# Line-filter.net
KiCad netlist of a schematic drawn in Altium Designer
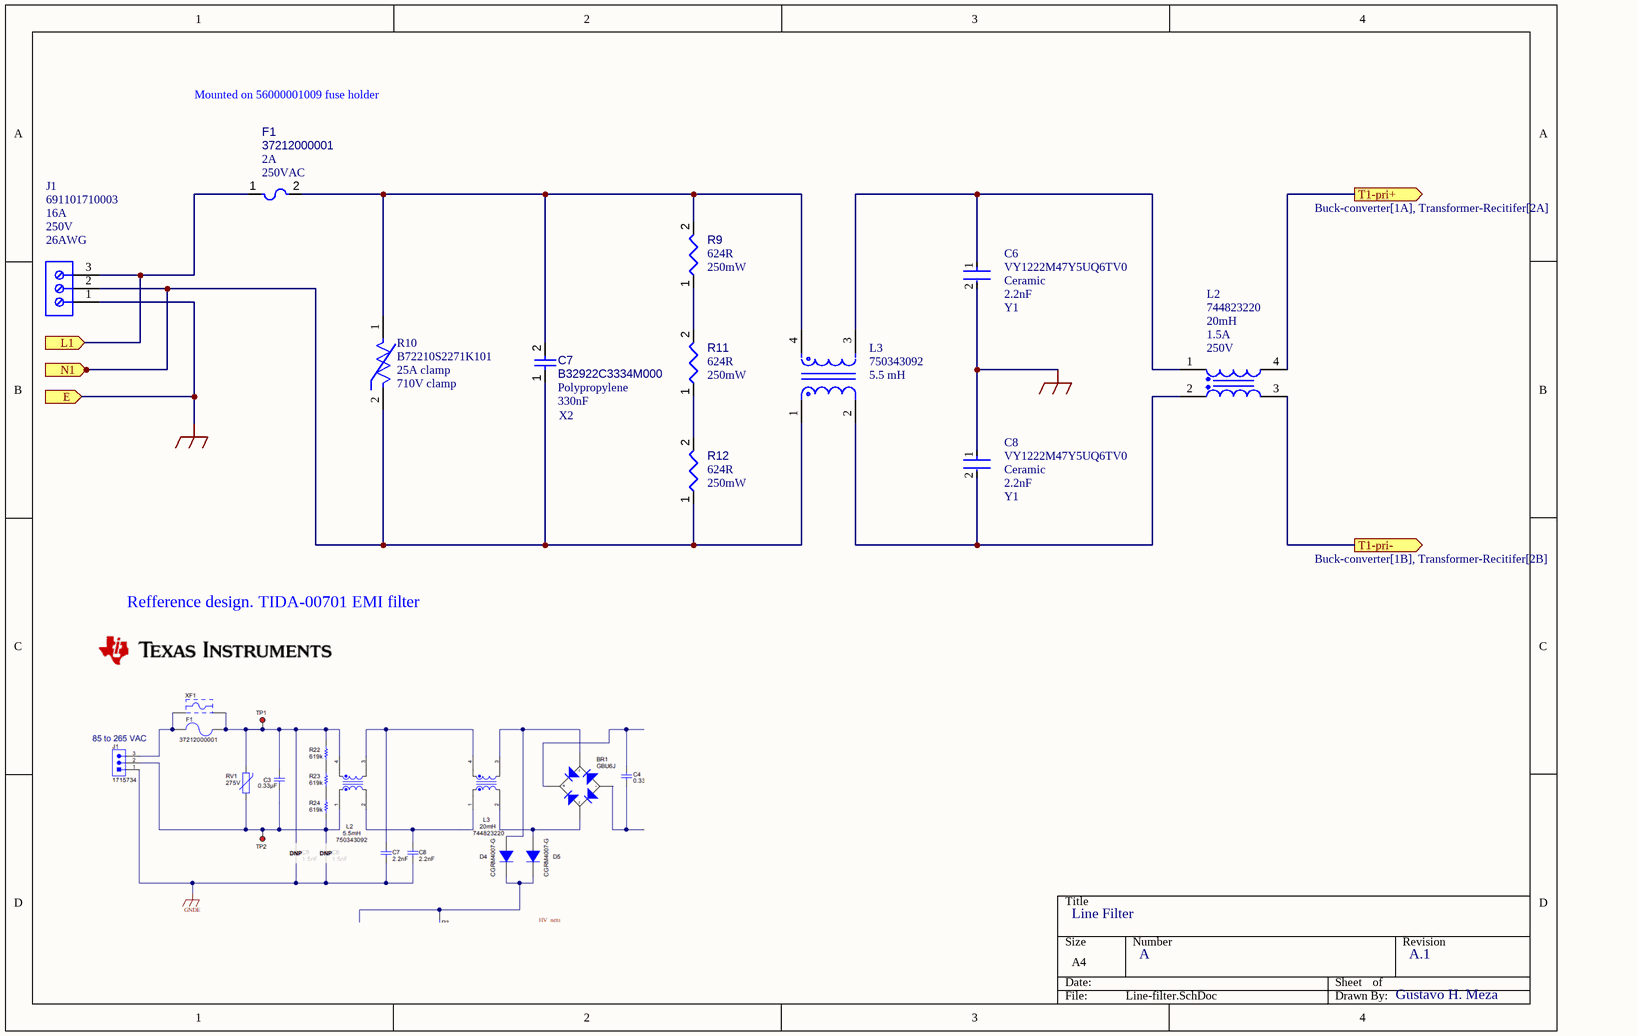
[diagram p0: Line-filter.SchDoc]

(export (version "E")
  (design (tool "Eeschema 10.0.6"))
  (components
    (comp (ref "C6")
      (value "VY1222M47Y5UQ6TV0")
      (footprint "FP-VY1470-MFG")
      (description "CAP CER 2200PF 760VAC Y5U RADIAL")
      (fields
        (field (name "RESISTOR TYPE") "Ceramic")
        (field (name "CAPACITANCE") "2.2nF")
        (field (name "VOLTAGE") "500V")
        (field (name "TOLERANCE") "20%")
        (field (name "SAFETY RATING") "Y1")
      )
      (libsource (lib "Altium Content Vault") (part "11868f565c42a9108669ba33697ecf6"))
    )
    (comp (ref "C7")
      (value "B32922C3334M000")
      (footprint "B32922C3334M000-Footprint-1")
      (description "Film Capacitor, Polypropylene, 630V, 20% +Tol, 20% -Tol, 0.33uF, Through Hole Mount")
      (fields
        (field (name "DIELECTRIC MATERIAL") "Polypropylene")
        (field (name "ALTIUM_VALUE") "330nF")
        (field (name "SAFETY RATING") "X2")
      )
      (libsource (lib "Cetys University") (part "CAP-NP-2"))
    )
    (comp (ref "C8")
      (value "VY1222M47Y5UQ6TV0")
      (footprint "FP-VY1470-MFG")
      (description "CAP CER 2200PF 760VAC Y5U RADIAL")
      (fields
        (field (name "RESISTOR TYPE") "Ceramic")
        (field (name "CAPACITANCE") "2.2nF")
        (field (name "VOLTAGE") "500V")
        (field (name "TOLERANCE") "20%")
        (field (name "SAFETY RATING") "Y1")
      )
      (libsource (lib "Altium Content Vault") (part "11868f565c42a9108669ba33697ecf6"))
    )
    (comp (ref "F1")
      (value "37212000001")
      (footprint "37212000001-Footprint-1")
      (description "Electric Fuse, Time Lag Blow, 2A, 250VAC, 35A (IR), Through Hole, TR5")
      (fields (field (name "CURRENT RATING") "2A") (field (name "VOLTAGE RATING") "250VAC"))
      (libsource (lib "Cetys University") (part "FUSE-2"))
    )
    (comp (ref "J1")
      (value "691101710003")
      (footprint "691101710003")
      (fields
        (field (name "VOLTAGE RATING") "250V")
        (field (name "CURRENT") "16A")
        (field (name "WIRE GAUGE (MIN)") "26AWG")
        (field (name "VOLTAGE") "250V")
      )
      (libsource (lib "Altium Content Vault") (part "TBL - 1R - 03P - Screw"))
    )
    (comp (ref "L2")
      (value "744823220")
      (footprint "WE-CMB_Type M_L23W13.8H25.5")
      (fields
        (field (name "VOLTAGE RATING") "250V")
        (field (name "CURRENT RATING") "1.5A")
        (field (name "INDUCTANCE") "20mH")
      )
      (libsource (lib "Altium Content Vault") (part "WE-CMB"))
    )
    (comp (ref "L3")
      (value "750343092")
      (footprint "FP-750343092-0")
      (description "Power Common Mode Choke")
      (fields (field (name "INDUCTANCE") "5.5 mH"))
      (libsource (lib "Altium Content Vault") (part "7e18bf8fdb9f2485ca2bcdf9073d69f"))
    )
    (comp (ref "R9")
      (value "624R")
      (footprint "RESC3216X06N")
      (fields
        (field (name "TOLERANCE") "1%")
        (field (name "POWER") "250mW")
        (field (name "Comment") "CRCW1206619KFKEA")
      )
      (libsource (lib "Cetys University") (part "RES-2"))
    )
    (comp (ref "R10")
      (value "B72210S2271K101")
      (footprint "FP-B72210S2271K101-MFG")
      (description "VARISTOR 430V 3.5KA DISC 10MM")
      (fields
        (field (name "CLAMPING CURRENT") "25A clamp")
        (field (name "OCTOPART") "https://octopart.com/b72210s2271k101-epcos-42227876")
        (field (name "MANUFACTURER") "EPCOS")
        (field (name "CLAMPING VOLTAGE") "710V clamp")
      )
      (libsource (lib "Altium Content Vault") (part "78a88060d5b7b043d6e48adc4284376"))
    )
    (comp (ref "R11")
      (value "624R")
      (footprint "RESC3216X06N")
      (fields
        (field (name "TOLERANCE") "1%")
        (field (name "POWER") "250mW")
        (field (name "Comment") "CRCW1206619KFKEA")
      )
      (libsource (lib "Cetys University") (part "RES-2"))
    )
    (comp (ref "R12")
      (value "624R")
      (footprint "RESC3216X06N")
      (fields
        (field (name "TOLERANCE") "1%")
        (field (name "POWER") "250mW")
        (field (name "Comment") "CRCW1206619KFKEA")
      )
      (libsource (lib "Cetys University") (part "RES-2"))
    )
  )
  (nets
    (net (code "1") (name "/L1") (class "Default")
      (node (ref "F1") (pin "1") (pinfunction "1_1") (pintype "passive"))
      (node (ref "J1") (pin "3") (pinfunction "3_3") (pintype "passive"))
    )
    (net (code "2") (name "/N1") (class "Default")
      (node (ref "C7") (pin "1") (pinfunction "1_1") (pintype "passive"))
      (node (ref "J1") (pin "2") (pinfunction "2_2") (pintype "passive"))
      (node (ref "L3") (pin "1") (pinfunction "1_1") (pintype "passive"))
      (node (ref "R10") (pin "2") (pinfunction "2_2") (pintype "passive"))
      (node (ref "R12") (pin "1") (pinfunction "1_1") (pintype "passive"))
    )
    (net (code "3") (name "/T1-pri+") (class "Default")
      (node (ref "L2") (pin "4") (pinfunction "4_4") (pintype "passive"))
    )
    (net (code "4") (name "/T1-pri-") (class "Default")
      (node (ref "L2") (pin "3") (pinfunction "3_3") (pintype "passive"))
    )
    (net (code "5") (name "GND") (class "Default")
      (node (ref "C6") (pin "2") (pinfunction "2_2") (pintype "passive"))
      (node (ref "C8") (pin "1") (pinfunction "1_1") (pintype "passive"))
      (node (ref "J1") (pin "1") (pinfunction "1_1") (pintype "passive"))
    )
    (net (code "6") (name "Net-(C6-Pad1)") (class "Default")
      (node (ref "C6") (pin "1") (pinfunction "1_1") (pintype "passive"))
      (node (ref "L2") (pin "1") (pinfunction "1_1") (pintype "passive"))
      (node (ref "L3") (pin "3") (pinfunction "3_3") (pintype "passive"))
    )
    (net (code "7") (name "Net-(C7-Pad2)") (class "Default")
      (node (ref "C7") (pin "2") (pinfunction "2_2") (pintype "passive"))
      (node (ref "F1") (pin "2") (pinfunction "2_2") (pintype "passive"))
      (node (ref "L3") (pin "4") (pinfunction "4_4") (pintype "passive"))
      (node (ref "R10") (pin "1") (pinfunction "1_1") (pintype "passive"))
      (node (ref "R9") (pin "2") (pinfunction "2_2") (pintype "passive"))
    )
    (net (code "8") (name "Net-(C8-Pad2)") (class "Default")
      (node (ref "C8") (pin "2") (pinfunction "2_2") (pintype "passive"))
      (node (ref "L2") (pin "2") (pinfunction "2_2") (pintype "passive"))
      (node (ref "L3") (pin "2") (pinfunction "2_2") (pintype "passive"))
    )
    (net (code "9") (name "Net-(R11-Pad1)") (class "Default")
      (node (ref "R11") (pin "1") (pinfunction "1_1") (pintype "passive"))
      (node (ref "R12") (pin "2") (pinfunction "2_2") (pintype "passive"))
    )
    (net (code "10") (name "Net-(R11-Pad2)") (class "Default")
      (node (ref "R11") (pin "2") (pinfunction "2_2") (pintype "passive"))
      (node (ref "R9") (pin "1") (pinfunction "1_1") (pintype "passive"))
    )
  )
)
